# EIS_Flow_Sensor.net
KiCad netlist of a schematic drawn in Altium Designer
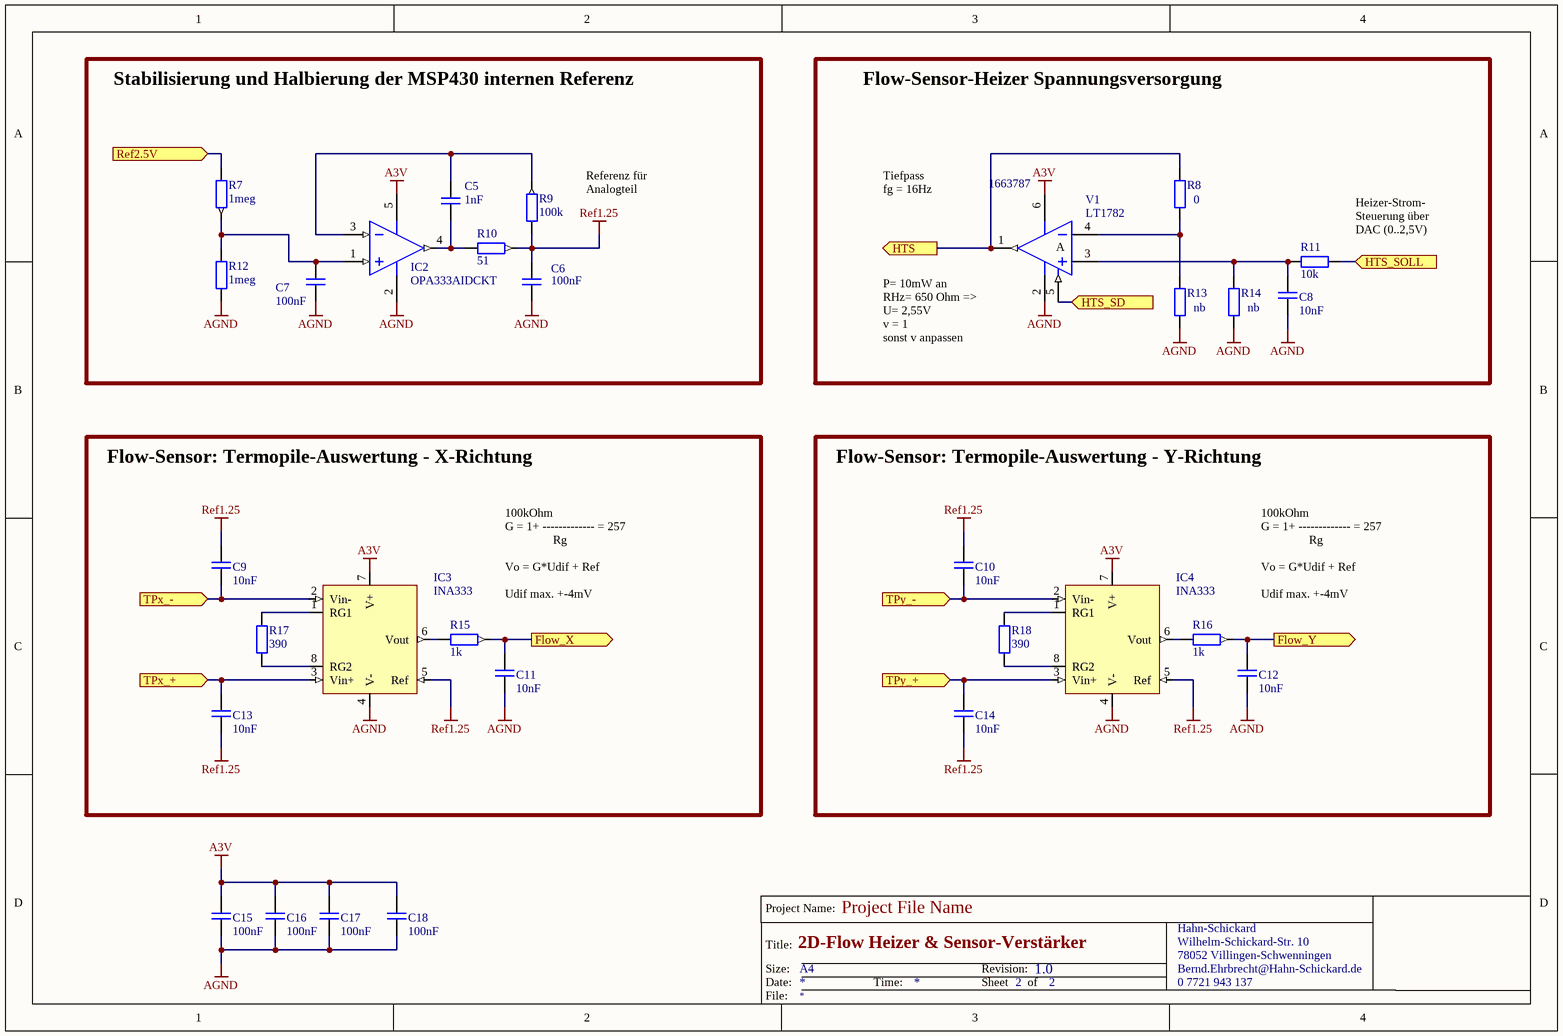
[diagram p0: EIS_Flow_Sensor.SchDoc]

(export (version "E")
  (design (tool "Eeschema 10.0.6"))
  (components
    (comp (ref "C5")
      (value "1nF")
      (footprint "CAPC1608N")
      (libsource (lib "My_Schlib_6_28") (part "Kondensator SMD Keramik"))
    )
    (comp (ref "C6")
      (value "100nF")
      (footprint "CAPC1608N")
      (libsource (lib "My_Schlib_6_28") (part "Kondensator SMD Keramik"))
    )
    (comp (ref "C7")
      (value "100nF")
      (footprint "CAPC1608N")
      (libsource (lib "My_Schlib_6_28") (part "Kondensator SMD Keramik"))
    )
    (comp (ref "C8")
      (value "10nF")
      (footprint "CAPC1608N")
      (libsource (lib "My_Schlib_6_28") (part "Kondensator SMD Keramik"))
    )
    (comp (ref "C9")
      (value "10nF")
      (footprint "CAPC1608N")
      (libsource (lib "My_Schlib_6_28") (part "Kondensator SMD Keramik"))
    )
    (comp (ref "C10")
      (value "10nF")
      (footprint "CAPC1608N")
      (libsource (lib "My_Schlib_6_28") (part "Kondensator SMD Keramik"))
    )
    (comp (ref "C11")
      (value "10nF")
      (footprint "CAPC1608N")
      (libsource (lib "My_Schlib_6_28") (part "Kondensator SMD Keramik"))
    )
    (comp (ref "C12")
      (value "10nF")
      (footprint "CAPC1608N")
      (libsource (lib "My_Schlib_6_28") (part "Kondensator SMD Keramik"))
    )
    (comp (ref "C13")
      (value "10nF")
      (footprint "CAPC1608N")
      (libsource (lib "My_Schlib_6_28") (part "Kondensator SMD Keramik"))
    )
    (comp (ref "C14")
      (value "10nF")
      (footprint "CAPC1608N")
      (libsource (lib "My_Schlib_6_28") (part "Kondensator SMD Keramik"))
    )
    (comp (ref "C15")
      (value "100nF")
      (footprint "CAPC1608N")
      (libsource (lib "My_Schlib_6_28") (part "Kondensator SMD Keramik"))
    )
    (comp (ref "C16")
      (value "100nF")
      (footprint "CAPC1608N")
      (libsource (lib "My_Schlib_6_28") (part "Kondensator SMD Keramik"))
    )
    (comp (ref "C17")
      (value "100nF")
      (footprint "CAPC1608N")
      (libsource (lib "My_Schlib_6_28") (part "Kondensator SMD Keramik"))
    )
    (comp (ref "C18")
      (value "100nF")
      (footprint "CAPC1608N")
      (libsource (lib "My_Schlib_6_28") (part "Kondensator SMD Keramik"))
    )
    (comp (ref "IC2")
      (value "OPA333AIDCKT")
      (footprint "TI-DCK5_V")
      (fields (field (name "MANUFACTURER") "Texas Instruments"))
      (libsource (lib "TI Amplifiers and Linear Operational Amplifier Precision Amplifier Part One") (part "OPA333AIDCKT"))
    )
    (comp (ref "IC3")
      (value "INA333")
      (footprint "TI-DRG8-2400X1450TP_V")
      (description "Instrumentation Amplifier")
      (fields (field (name "PUBLISHER") "HSG Jürgen Merz"))
      (libsource (lib "HSG-IMIT") (part "INA333"))
    )
    (comp (ref "IC4")
      (value "INA333")
      (footprint "TI-DRG8-2400X1450TP_V")
      (description "Instrumentation Amplifier")
      (fields (field (name "PUBLISHER") "HSG Jürgen Merz"))
      (libsource (lib "HSG-IMIT") (part "INA333"))
    )
    (comp (ref "R7")
      (value "1meg")
      (footprint "RESC1608N")
      (libsource (lib "My_Schlib_6_28") (part "Widerstand SMD"))
    )
    (comp (ref "R8")
      (value "0")
      (footprint "RESC1608N")
      (libsource (lib "My_Schlib_6_28") (part "Widerstand SMD"))
    )
    (comp (ref "R9")
      (value "100k")
      (footprint "RESC1608N")
      (libsource (lib "My_Schlib_6_28") (part "Widerstand SMD"))
    )
    (comp (ref "R10")
      (value "51")
      (footprint "RESC1608N")
      (libsource (lib "My_Schlib_6_28") (part "Widerstand SMD"))
    )
    (comp (ref "R11")
      (value "10k")
      (footprint "RESC1608N")
      (libsource (lib "My_Schlib_6_28") (part "Widerstand SMD"))
    )
    (comp (ref "R12")
      (value "1meg")
      (footprint "RESC1608N")
      (libsource (lib "My_Schlib_6_28") (part "Widerstand SMD"))
    )
    (comp (ref "R13")
      (value "nb")
      (footprint "RESC1608N")
      (libsource (lib "My_Schlib_6_28") (part "Widerstand SMD"))
    )
    (comp (ref "R14")
      (value "nb")
      (footprint "RESC1608N")
      (libsource (lib "My_Schlib_6_28") (part "Widerstand SMD"))
    )
    (comp (ref "R15")
      (value "1k")
      (footprint "RESC1608N")
      (libsource (lib "My_Schlib_6_28") (part "Widerstand SMD"))
    )
    (comp (ref "R16")
      (value "1k")
      (footprint "RESC1608N")
      (libsource (lib "My_Schlib_6_28") (part "Widerstand SMD"))
    )
    (comp (ref "R17")
      (value "390")
      (footprint "RESC1608N")
      (libsource (lib "My_Schlib_6_28") (part "Widerstand SMD"))
    )
    (comp (ref "R18")
      (value "390")
      (footprint "RESC1608N")
      (libsource (lib "My_Schlib_6_28") (part "Widerstand SMD"))
    )
    (comp (ref "V1")
      (value "LT1782")
      (footprint "SOT23-6")
      (fields (field (name "SUPPLIER PART NUMBER 1") "1663787"))
      (libsource (lib "My_Schlib_6_27") (part "LT1782_SD"))
    )
  )
  (nets
    (net (code "1") (name "/Flow_X") (class "Default")
      (node (ref "C11") (pin "2") (pinfunction "2_2") (pintype "passive"))
      (node (ref "R15") (pin "1") (pinfunction "1_1") (pintype "passive"))
    )
    (net (code "2") (name "/Flow_Y") (class "Default")
      (node (ref "C12") (pin "2") (pinfunction "2_2") (pintype "passive"))
      (node (ref "R16") (pin "1") (pinfunction "1_1") (pintype "passive"))
    )
    (net (code "3") (name "/HTS") (class "Default")
      (node (ref "R8") (pin "2") (pinfunction "2_2") (pintype "passive"))
      (node (ref "V1") (pin "1") (pinfunction "OUT_1") (pintype "output"))
    )
    (net (code "4") (name "/HTS_SD") (class "Default")
      (node (ref "V1") (pin "5") (pinfunction "Shdn_5") (pintype "input"))
    )
    (net (code "5") (name "/HTS_SOLL") (class "Default")
      (node (ref "R11") (pin "1") (pinfunction "1_1") (pintype "passive"))
    )
    (net (code "6") (name "/Ref2.5V") (class "Default")
      (node (ref "R7") (pin "1") (pinfunction "1_1") (pintype "passive"))
    )
    (net (code "7") (name "/TPx_+") (class "Default")
      (node (ref "C13") (pin "1") (pinfunction "1_1") (pintype "passive"))
      (node (ref "IC3") (pin "3") (pinfunction "Vin+_3") (pintype "input"))
    )
    (net (code "8") (name "/TPx_-") (class "Default")
      (node (ref "C9") (pin "2") (pinfunction "2_2") (pintype "passive"))
      (node (ref "IC3") (pin "2") (pinfunction "Vin-_2") (pintype "input"))
    )
    (net (code "9") (name "/TPy_+") (class "Default")
      (node (ref "C14") (pin "1") (pinfunction "1_1") (pintype "passive"))
      (node (ref "IC4") (pin "3") (pinfunction "Vin+_3") (pintype "input"))
    )
    (net (code "10") (name "/TPy_-") (class "Default")
      (node (ref "C10") (pin "2") (pinfunction "2_2") (pintype "passive"))
      (node (ref "IC4") (pin "2") (pinfunction "Vin-_2") (pintype "input"))
    )
    (net (code "11") (name "A3V") (class "Default")
      (node (ref "C15") (pin "1") (pinfunction "1_1") (pintype "passive"))
      (node (ref "C16") (pin "1") (pinfunction "1_1") (pintype "passive"))
      (node (ref "C17") (pin "1") (pinfunction "1_1") (pintype "passive"))
      (node (ref "C18") (pin "2") (pinfunction "2_2") (pintype "passive"))
      (node (ref "IC2") (pin "5") (pinfunction "V+_5") (pintype "power_in"))
      (node (ref "IC3") (pin "7") (pinfunction "V+_7") (pintype "power_in"))
      (node (ref "IC4") (pin "7") (pinfunction "V+_7") (pintype "power_in"))
      (node (ref "V1") (pin "6") (pinfunction "V+_6") (pintype "power_in"))
    )
    (net (code "12") (name "AGND") (class "Default")
      (node (ref "C11") (pin "1") (pinfunction "1_1") (pintype "passive"))
      (node (ref "C12") (pin "1") (pinfunction "1_1") (pintype "passive"))
      (node (ref "C15") (pin "2") (pinfunction "2_2") (pintype "passive"))
      (node (ref "C16") (pin "2") (pinfunction "2_2") (pintype "passive"))
      (node (ref "C17") (pin "2") (pinfunction "2_2") (pintype "passive"))
      (node (ref "C18") (pin "1") (pinfunction "1_1") (pintype "passive"))
      (node (ref "C6") (pin "2") (pinfunction "2_2") (pintype "passive"))
      (node (ref "C7") (pin "2") (pinfunction "2_2") (pintype "passive"))
      (node (ref "C8") (pin "1") (pinfunction "1_1") (pintype "passive"))
      (node (ref "IC2") (pin "2") (pinfunction "V-_2") (pintype "power_in"))
      (node (ref "IC3") (pin "4") (pinfunction "V-_4") (pintype "power_in"))
      (node (ref "IC4") (pin "4") (pinfunction "V-_4") (pintype "power_in"))
      (node (ref "R12") (pin "2") (pinfunction "2_2") (pintype "passive"))
      (node (ref "R13") (pin "1") (pinfunction "1_1") (pintype "passive"))
      (node (ref "R14") (pin "1") (pinfunction "1_1") (pintype "passive"))
      (node (ref "V1") (pin "2") (pinfunction "V-_2") (pintype "power_in"))
    )
    (net (code "13") (name "Net-(IC2-IN+)") (class "Default")
      (node (ref "C7") (pin "1") (pinfunction "1_1") (pintype "passive"))
      (node (ref "IC2") (pin "1") (pinfunction "IN+_1") (pintype "input"))
      (node (ref "R12") (pin "1") (pinfunction "1_1") (pintype "passive"))
      (node (ref "R7") (pin "2") (pinfunction "2_2") (pintype "passive"))
    )
    (net (code "14") (name "Net-(IC2-IN-)") (class "Default")
      (node (ref "C5") (pin "1") (pinfunction "1_1") (pintype "passive"))
      (node (ref "IC2") (pin "3") (pinfunction "IN-_3") (pintype "input"))
      (node (ref "R9") (pin "1") (pinfunction "1_1") (pintype "passive"))
    )
    (net (code "15") (name "Net-(IC2-OUT)") (class "Default")
      (node (ref "C5") (pin "2") (pinfunction "2_2") (pintype "passive"))
      (node (ref "IC2") (pin "4") (pinfunction "OUT_4") (pintype "output"))
      (node (ref "R10") (pin "2") (pinfunction "2_2") (pintype "passive"))
    )
    (net (code "16") (name "Net-(IC3-RG1)") (class "Default")
      (node (ref "IC3") (pin "1") (pinfunction "RG1_1") (pintype "passive"))
      (node (ref "R17") (pin "2") (pinfunction "2_2") (pintype "passive"))
    )
    (net (code "17") (name "Net-(IC3-RG2)") (class "Default")
      (node (ref "IC3") (pin "8") (pinfunction "RG2_8") (pintype "passive"))
      (node (ref "R17") (pin "1") (pinfunction "1_1") (pintype "passive"))
    )
    (net (code "18") (name "Net-(IC3-Vout)") (class "Default")
      (node (ref "IC3") (pin "6") (pinfunction "Vout_6") (pintype "output"))
      (node (ref "R15") (pin "2") (pinfunction "2_2") (pintype "passive"))
    )
    (net (code "19") (name "Net-(IC4-RG1)") (class "Default")
      (node (ref "IC4") (pin "1") (pinfunction "RG1_1") (pintype "passive"))
      (node (ref "R18") (pin "2") (pinfunction "2_2") (pintype "passive"))
    )
    (net (code "20") (name "Net-(IC4-RG2)") (class "Default")
      (node (ref "IC4") (pin "8") (pinfunction "RG2_8") (pintype "passive"))
      (node (ref "R18") (pin "1") (pinfunction "1_1") (pintype "passive"))
    )
    (net (code "21") (name "Net-(IC4-Vout)") (class "Default")
      (node (ref "IC4") (pin "6") (pinfunction "Vout_6") (pintype "output"))
      (node (ref "R16") (pin "2") (pinfunction "2_2") (pintype "passive"))
    )
    (net (code "22") (name "Net-(V1-IN+)") (class "Default")
      (node (ref "C8") (pin "2") (pinfunction "2_2") (pintype "passive"))
      (node (ref "R11") (pin "2") (pinfunction "2_2") (pintype "passive"))
      (node (ref "R14") (pin "2") (pinfunction "2_2") (pintype "passive"))
      (node (ref "V1") (pin "3") (pinfunction "IN+_3") (pintype "passive"))
    )
    (net (code "23") (name "Net-(V1-IN-)") (class "Default")
      (node (ref "R13") (pin "2") (pinfunction "2_2") (pintype "passive"))
      (node (ref "R8") (pin "1") (pinfunction "1_1") (pintype "passive"))
      (node (ref "V1") (pin "4") (pinfunction "IN-_4") (pintype "passive"))
    )
    (net (code "24") (name "Ref1.25") (class "Default")
      (node (ref "C10") (pin "1") (pinfunction "1_1") (pintype "passive"))
      (node (ref "C13") (pin "2") (pinfunction "2_2") (pintype "passive"))
      (node (ref "C14") (pin "2") (pinfunction "2_2") (pintype "passive"))
      (node (ref "C6") (pin "1") (pinfunction "1_1") (pintype "passive"))
      (node (ref "C9") (pin "1") (pinfunction "1_1") (pintype "passive"))
      (node (ref "IC3") (pin "5") (pinfunction "Ref_5") (pintype "input"))
      (node (ref "IC4") (pin "5") (pinfunction "Ref_5") (pintype "input"))
      (node (ref "R10") (pin "1") (pinfunction "1_1") (pintype "passive"))
      (node (ref "R9") (pin "2") (pinfunction "2_2") (pintype "passive"))
    )
  )
)
